# PCB.net
KiCad netlist of a schematic drawn in EAGLE
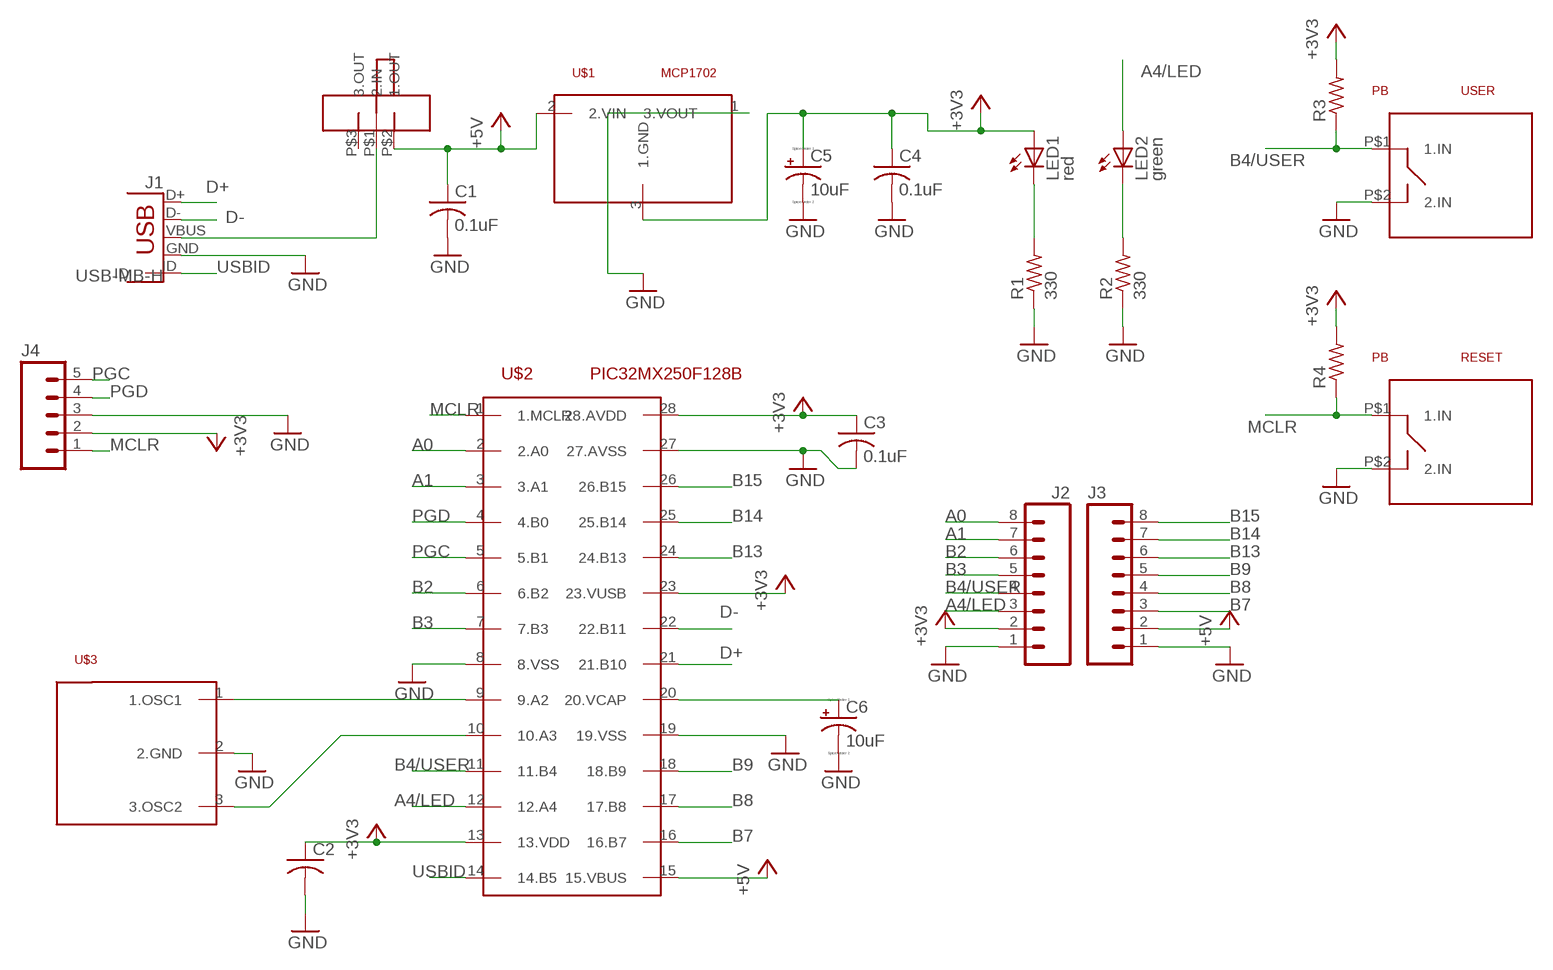
[diagram p0: schematic, sheet 1]

(export (version "E")
  (design (tool "Eeschema 10.0.6"))
  (components
    (comp (ref "C1")
      (value "0.1uF")
      (footprint "eagle-import:C025-025X050")
      (libsource (lib "eagle-import") (part "C-US025-025X050"))
    )
    (comp (ref "C2")
      (value "C-US025-025X050")
      (footprint "eagle-import:C025-025X050")
      (libsource (lib "eagle-import") (part "C-US025-025X050"))
    )
    (comp (ref "C3")
      (value "0.1uF")
      (footprint "eagle-import:C025-025X050")
      (libsource (lib "eagle-import") (part "C-US025-025X050"))
    )
    (comp (ref "C4")
      (value "0.1uF")
      (footprint "eagle-import:C025-025X050")
      (libsource (lib "eagle-import") (part "C-US025-025X050"))
    )
    (comp (ref "C5")
      (value "10uF")
      (footprint "eagle-import:B45181A")
      (libsource (lib "eagle-import") (part "CPOL-USB45181A"))
    )
    (comp (ref "C6")
      (value "10uF")
      (footprint "eagle-import:B45181A")
      (libsource (lib "eagle-import") (part "CPOL-USB45181A"))
    )
    (comp (ref "J1")
      (value "USB-MB-H")
      (footprint "eagle-import:USB-MB-H")
      (libsource (lib "eagle-import") (part "USB-MB-H"))
    )
    (comp (ref "J2")
      (value "M08")
      (footprint "eagle-import:1X08_ROUND")
      (libsource (lib "eagle-import") (part "M08"))
    )
    (comp (ref "J3")
      (value "M08")
      (footprint "eagle-import:1X08_ROUND")
      (libsource (lib "eagle-import") (part "M08"))
    )
    (comp (ref "J4")
      (value "M05PTH")
      (footprint "eagle-import:1X05")
      (libsource (lib "eagle-import") (part "M05PTH"))
    )
    (comp (ref "LED1")
      (value "red")
      (footprint "eagle-import:LED3MM")
      (libsource (lib "eagle-import") (part "LED3MM"))
    )
    (comp (ref "LED2")
      (value "green")
      (footprint "eagle-import:LED3MM")
      (libsource (lib "eagle-import") (part "LED3MM"))
    )
    (comp (ref "R1")
      (value "330")
      (footprint "eagle-import:0207_10")
      (libsource (lib "eagle-import") (part "R-US_0207/10"))
    )
    (comp (ref "R2")
      (value "330")
      (footprint "eagle-import:0207_10")
      (libsource (lib "eagle-import") (part "R-US_0207/10"))
    )
    (comp (ref "R3")
      (value "R-US_0207/10")
      (footprint "eagle-import:0207_10")
      (libsource (lib "eagle-import") (part "R-US_0207/10"))
    )
    (comp (ref "R4")
      (value "R-US_0207/10")
      (footprint "eagle-import:0207_10")
      (libsource (lib "eagle-import") (part "R-US_0207/10"))
    )
    (comp (ref "RESET")
      (value "PB")
      (footprint "eagle-import:PUSHBUTTON")
      (libsource (lib "eagle-import") (part "PB"))
    )
    (comp (ref "U$1")
      (value "MCP1702")
      (footprint "eagle-import:TO92")
      (libsource (lib "eagle-import") (part "MCP1702"))
    )
    (comp (ref "U$2")
      (value "PIC32MX250F128B")
      (footprint "eagle-import:DIL28-3")
      (libsource (lib "eagle-import") (part "PIC32MX250F128B"))
    )
    (comp (ref "U$3")
      (value "CRES")
      (footprint "eagle-import:1X03")
      (libsource (lib "eagle-import") (part "CRES"))
    )
    (comp (ref "U$4")
      (value "SLIDE")
      (footprint "eagle-import:SLIDE")
      (libsource (lib "eagle-import") (part "SLIDE"))
    )
    (comp (ref "USER")
      (value "PB")
      (footprint "eagle-import:PUSHBUTTON")
      (libsource (lib "eagle-import") (part "PB"))
    )
  )
  (nets
    (net (code "1") (name "+3V3") (class "Default")
      (node (ref "C2") (pin "1") (pinfunction "1_1") (pintype "passive"))
      (node (ref "C3") (pin "1") (pinfunction "1_1") (pintype "passive"))
      (node (ref "C4") (pin "1") (pinfunction "1_1") (pintype "passive"))
      (node (ref "C5") (pin "+") (pinfunction "+_+") (pintype "passive"))
      (node (ref "J2") (pin "2") (pinfunction "2_2") (pintype "passive"))
      (node (ref "J4") (pin "2") (pinfunction "2_2") (pintype "passive"))
      (node (ref "LED1") (pin "A") (pinfunction "A_A") (pintype "passive"))
      (node (ref "R3") (pin "2") (pinfunction "2_2") (pintype "passive"))
      (node (ref "R4") (pin "2") (pinfunction "2_2") (pintype "passive"))
      (node (ref "U$1") (pin "3") (pinfunction "1.GND_3") (pintype "bidirectional"))
      (node (ref "U$2") (pin "13") (pinfunction "13.VDD_13") (pintype "bidirectional"))
      (node (ref "U$2") (pin "23") (pinfunction "23.VUSB_23") (pintype "bidirectional"))
      (node (ref "U$2") (pin "28") (pinfunction "28.AVDD_28") (pintype "bidirectional"))
    )
    (net (code "2") (name "+5V") (class "Default")
      (node (ref "C1") (pin "1") (pinfunction "1_1") (pintype "passive"))
      (node (ref "J3") (pin "2") (pinfunction "2_2") (pintype "passive"))
      (node (ref "U$1") (pin "2") (pinfunction "2.VIN_2") (pintype "bidirectional"))
      (node (ref "U$2") (pin "15") (pinfunction "15.VBUS_15") (pintype "bidirectional"))
      (node (ref "U$4") (pin "P$2") (pinfunction "1.OUT_P$2") (pintype "bidirectional"))
    )
    (net (code "3") (name "/A0") (class "Default")
      (node (ref "J2") (pin "8") (pinfunction "8_8") (pintype "passive"))
      (node (ref "U$2") (pin "2") (pinfunction "2.A0_2") (pintype "bidirectional"))
    )
    (net (code "4") (name "/A1") (class "Default")
      (node (ref "J2") (pin "7") (pinfunction "7_7") (pintype "passive"))
      (node (ref "U$2") (pin "3") (pinfunction "3.A1_3") (pintype "bidirectional"))
    )
    (net (code "5") (name "/A4{slash}LED") (class "Default")
      (node (ref "J2") (pin "3") (pinfunction "3_3") (pintype "passive"))
      (node (ref "LED2") (pin "A") (pinfunction "A_A") (pintype "passive"))
      (node (ref "U$2") (pin "12") (pinfunction "12.A4_12") (pintype "bidirectional"))
    )
    (net (code "6") (name "/B2") (class "Default")
      (node (ref "J2") (pin "6") (pinfunction "6_6") (pintype "passive"))
      (node (ref "U$2") (pin "6") (pinfunction "6.B2_6") (pintype "bidirectional"))
    )
    (net (code "7") (name "/B3") (class "Default")
      (node (ref "J2") (pin "5") (pinfunction "5_5") (pintype "passive"))
      (node (ref "U$2") (pin "7") (pinfunction "7.B3_7") (pintype "bidirectional"))
    )
    (net (code "8") (name "/B4{slash}USER") (class "Default")
      (node (ref "J2") (pin "4") (pinfunction "4_4") (pintype "passive"))
      (node (ref "R3") (pin "1") (pinfunction "1_1") (pintype "passive"))
      (node (ref "U$2") (pin "11") (pinfunction "11.B4_11") (pintype "bidirectional"))
      (node (ref "USER") (pin "P$1") (pinfunction "1.IN_P$1") (pintype "bidirectional"))
    )
    (net (code "9") (name "/B7") (class "Default")
      (node (ref "J3") (pin "3") (pinfunction "3_3") (pintype "passive"))
      (node (ref "U$2") (pin "16") (pinfunction "16.B7_16") (pintype "bidirectional"))
    )
    (net (code "10") (name "/B8") (class "Default")
      (node (ref "J3") (pin "4") (pinfunction "4_4") (pintype "passive"))
      (node (ref "U$2") (pin "17") (pinfunction "17.B8_17") (pintype "bidirectional"))
    )
    (net (code "11") (name "/B9") (class "Default")
      (node (ref "J3") (pin "5") (pinfunction "5_5") (pintype "passive"))
      (node (ref "U$2") (pin "18") (pinfunction "18.B9_18") (pintype "bidirectional"))
    )
    (net (code "12") (name "/B13") (class "Default")
      (node (ref "J3") (pin "6") (pinfunction "6_6") (pintype "passive"))
      (node (ref "U$2") (pin "24") (pinfunction "24.B13_24") (pintype "bidirectional"))
    )
    (net (code "13") (name "/B14") (class "Default")
      (node (ref "J3") (pin "7") (pinfunction "7_7") (pintype "passive"))
      (node (ref "U$2") (pin "25") (pinfunction "25.B14_25") (pintype "bidirectional"))
    )
    (net (code "14") (name "/B15") (class "Default")
      (node (ref "J3") (pin "8") (pinfunction "8_8") (pintype "passive"))
      (node (ref "U$2") (pin "26") (pinfunction "26.B15_26") (pintype "bidirectional"))
    )
    (net (code "15") (name "/D+") (class "Default")
      (node (ref "J1") (pin "D+") (pinfunction "D+_D+") (pintype "bidirectional"))
      (node (ref "U$2") (pin "21") (pinfunction "21.B10_21") (pintype "bidirectional"))
    )
    (net (code "16") (name "/D-") (class "Default")
      (node (ref "J1") (pin "D-") (pinfunction "D-_D-") (pintype "bidirectional"))
      (node (ref "U$2") (pin "22") (pinfunction "22.B11_22") (pintype "bidirectional"))
    )
    (net (code "17") (name "/MCLR") (class "Default")
      (node (ref "J4") (pin "1") (pinfunction "1_1") (pintype "passive"))
      (node (ref "R4") (pin "1") (pinfunction "1_1") (pintype "passive"))
      (node (ref "RESET") (pin "P$1") (pinfunction "1.IN_P$1") (pintype "bidirectional"))
      (node (ref "U$2") (pin "1") (pinfunction "1.MCLR_1") (pintype "bidirectional"))
    )
    (net (code "18") (name "/PGC") (class "Default")
      (node (ref "J4") (pin "5") (pinfunction "5_5") (pintype "passive"))
      (node (ref "U$2") (pin "5") (pinfunction "5.B1_5") (pintype "bidirectional"))
    )
    (net (code "19") (name "/PGD") (class "Default")
      (node (ref "J4") (pin "4") (pinfunction "4_4") (pintype "passive"))
      (node (ref "U$2") (pin "4") (pinfunction "4.B0_4") (pintype "bidirectional"))
    )
    (net (code "20") (name "/USBID") (class "Default")
      (node (ref "J1") (pin "ID") (pinfunction "ID_ID") (pintype "bidirectional"))
      (node (ref "U$2") (pin "14") (pinfunction "14.B5_14") (pintype "bidirectional"))
    )
    (net (code "21") (name "GND") (class "Default")
      (node (ref "C1") (pin "2") (pinfunction "2_2") (pintype "passive"))
      (node (ref "C2") (pin "2") (pinfunction "2_2") (pintype "passive"))
      (node (ref "C3") (pin "2") (pinfunction "2_2") (pintype "passive"))
      (node (ref "C4") (pin "2") (pinfunction "2_2") (pintype "passive"))
      (node (ref "C5") (pin "-") (pinfunction "-_-") (pintype "passive"))
      (node (ref "C6") (pin "-") (pinfunction "-_-") (pintype "passive"))
      (node (ref "J1") (pin "GND") (pinfunction "GND_GND") (pintype "bidirectional"))
      (node (ref "J2") (pin "1") (pinfunction "1_1") (pintype "passive"))
      (node (ref "J3") (pin "1") (pinfunction "1_1") (pintype "passive"))
      (node (ref "J4") (pin "3") (pinfunction "3_3") (pintype "passive"))
      (node (ref "R1") (pin "1") (pinfunction "1_1") (pintype "passive"))
      (node (ref "R2") (pin "1") (pinfunction "1_1") (pintype "passive"))
      (node (ref "RESET") (pin "P$2") (pinfunction "2.IN_P$2") (pintype "bidirectional"))
      (node (ref "U$1") (pin "1") (pinfunction "3.VOUT_1") (pintype "bidirectional"))
      (node (ref "U$2") (pin "19") (pinfunction "19.VSS_19") (pintype "bidirectional"))
      (node (ref "U$2") (pin "27") (pinfunction "27.AVSS_27") (pintype "bidirectional"))
      (node (ref "U$2") (pin "8") (pinfunction "8.VSS_8") (pintype "bidirectional"))
      (node (ref "U$3") (pin "2") (pinfunction "2.GND_2") (pintype "bidirectional"))
      (node (ref "USER") (pin "P$2") (pinfunction "2.IN_P$2") (pintype "bidirectional"))
    )
    (net (code "22") (name "Net-(LED1-C)") (class "Default")
      (node (ref "LED1") (pin "K") (pinfunction "C_K") (pintype "passive"))
      (node (ref "R1") (pin "2") (pinfunction "2_2") (pintype "passive"))
    )
    (net (code "23") (name "Net-(LED2-C)") (class "Default")
      (node (ref "LED2") (pin "K") (pinfunction "C_K") (pintype "passive"))
      (node (ref "R2") (pin "2") (pinfunction "2_2") (pintype "passive"))
    )
    (net (code "24") (name "Net-(U$2-9.A2)") (class "Default")
      (node (ref "U$2") (pin "9") (pinfunction "9.A2_9") (pintype "bidirectional"))
      (node (ref "U$3") (pin "1") (pinfunction "1.OSC1_1") (pintype "bidirectional"))
    )
    (net (code "25") (name "Net-(U$2-10.A3)") (class "Default")
      (node (ref "U$2") (pin "10") (pinfunction "10.A3_10") (pintype "bidirectional"))
      (node (ref "U$3") (pin "3") (pinfunction "3.OSC2_3") (pintype "bidirectional"))
    )
    (net (code "26") (name "Net-(U$2-20.VCAP)") (class "Default")
      (node (ref "C6") (pin "+") (pinfunction "+_+") (pintype "passive"))
      (node (ref "U$2") (pin "20") (pinfunction "20.VCAP_20") (pintype "bidirectional"))
    )
    (net (code "27") (name "Net-(U$4-2.IN)") (class "Default")
      (node (ref "J1") (pin "VBUS") (pinfunction "VBUS_VBUS") (pintype "bidirectional"))
      (node (ref "U$4") (pin "P$1") (pinfunction "2.IN_P$1") (pintype "bidirectional"))
    )
    (net (code "28") (name "unconnected-(U$4-3.OUT-PadP$3)") (class "Default")
      (node (ref "U$4") (pin "P$3") (pinfunction "3.OUT_P$3") (pintype "bidirectional"))
    )
  )
)
